# POWER_SUPPLY_20-100V.net
KiCad netlist of a schematic drawn in Altium Designer
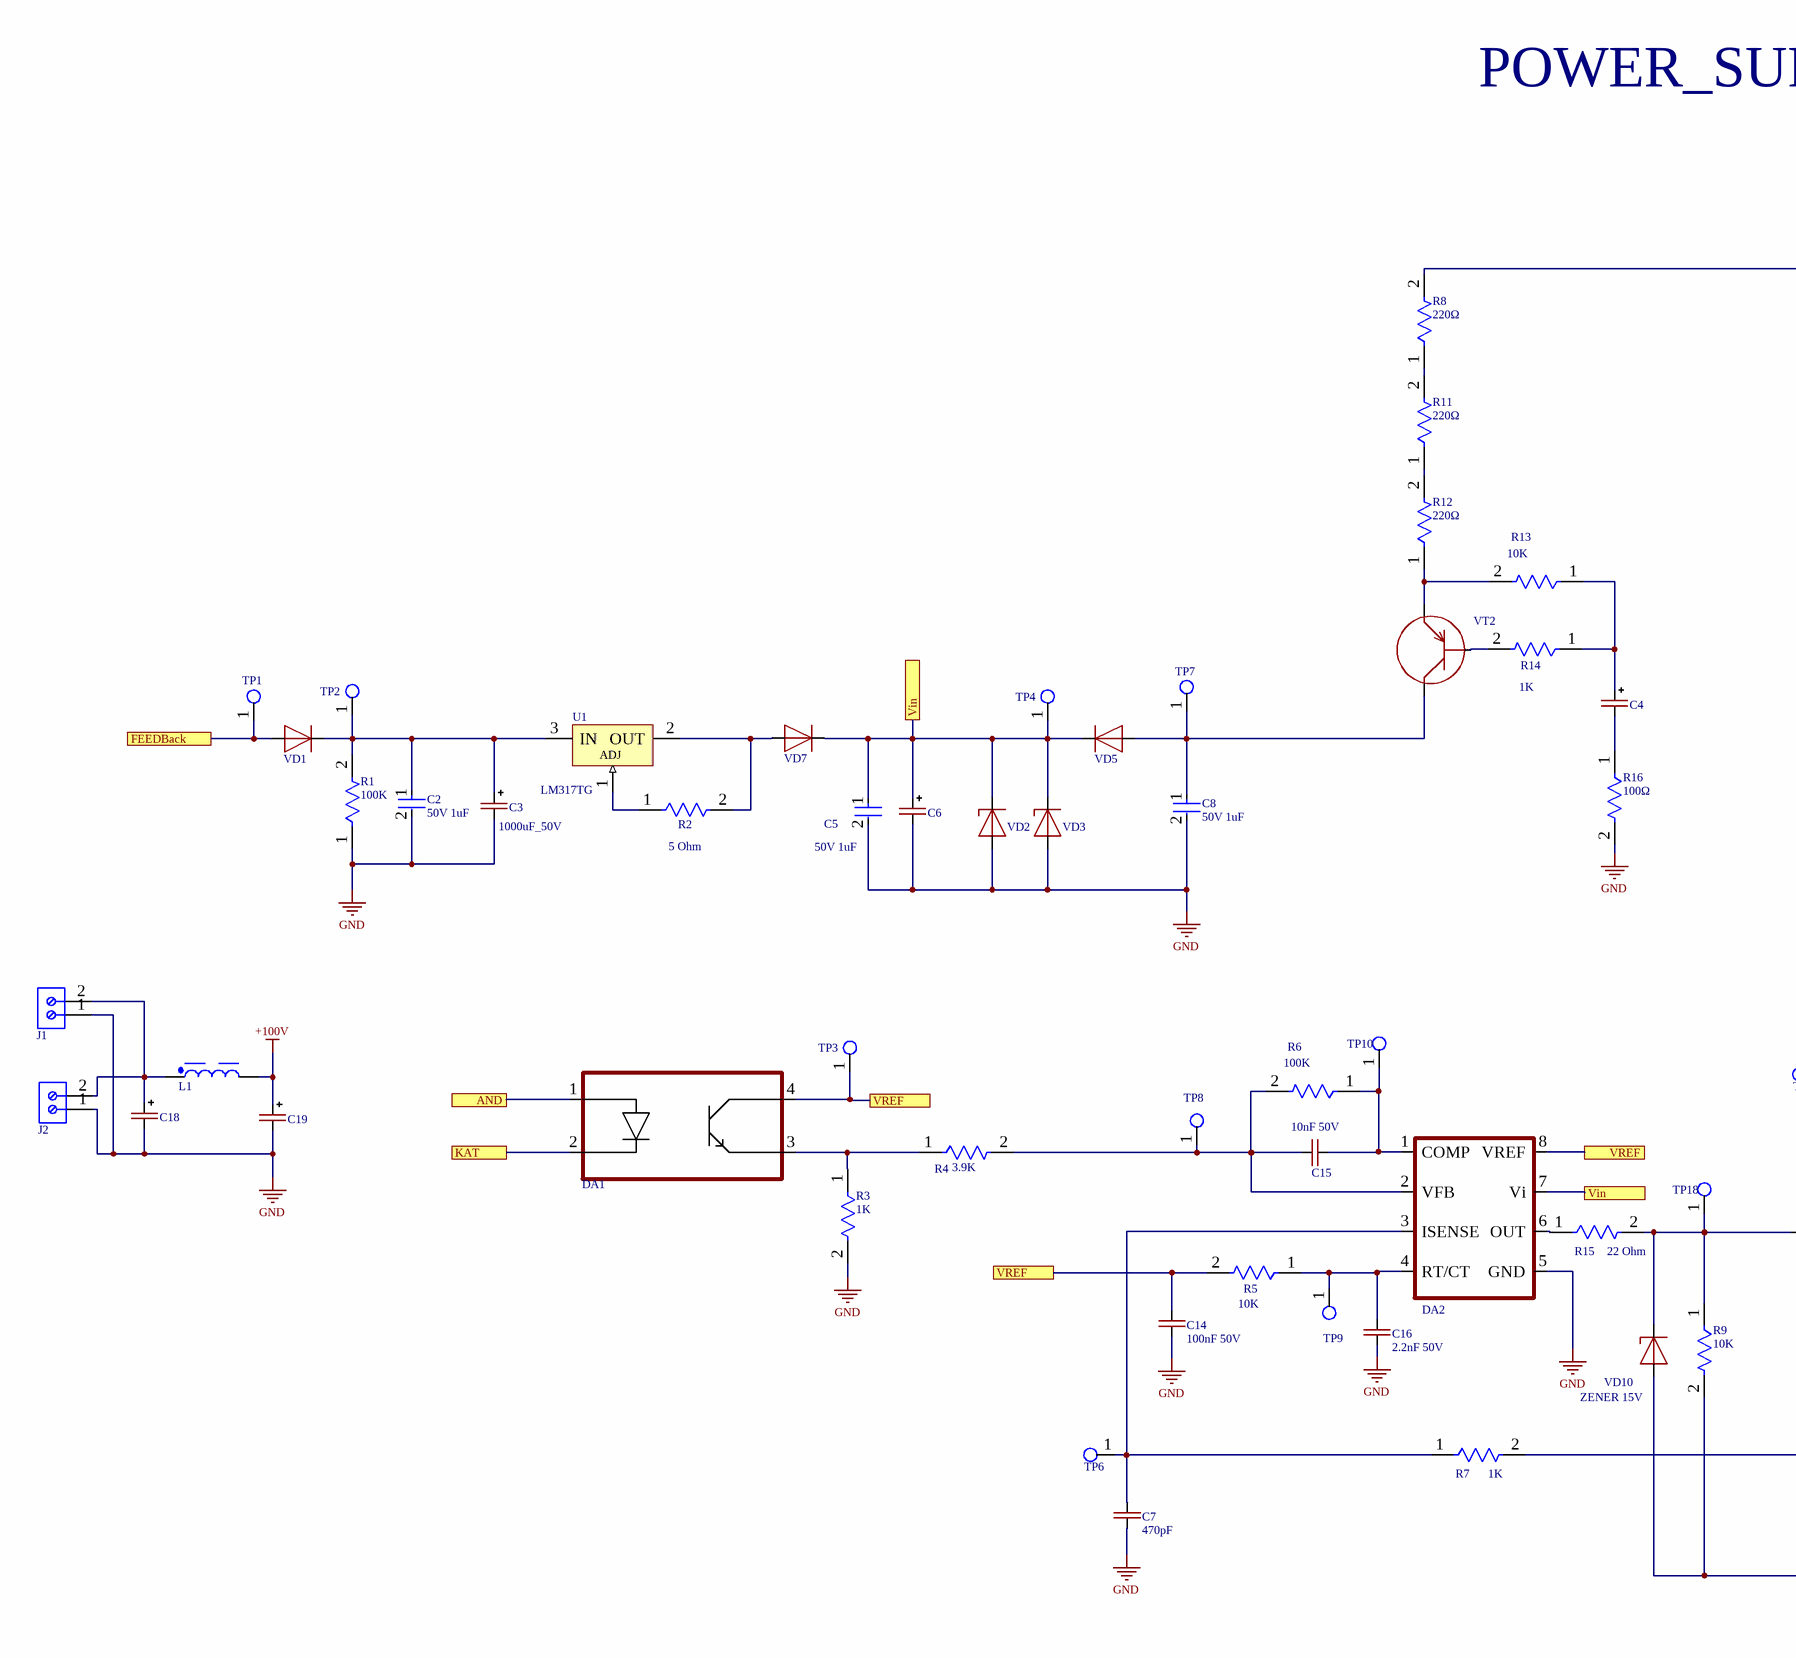
[diagram p0: POWER_SUPPLY_20-100V.SchDoc, left]
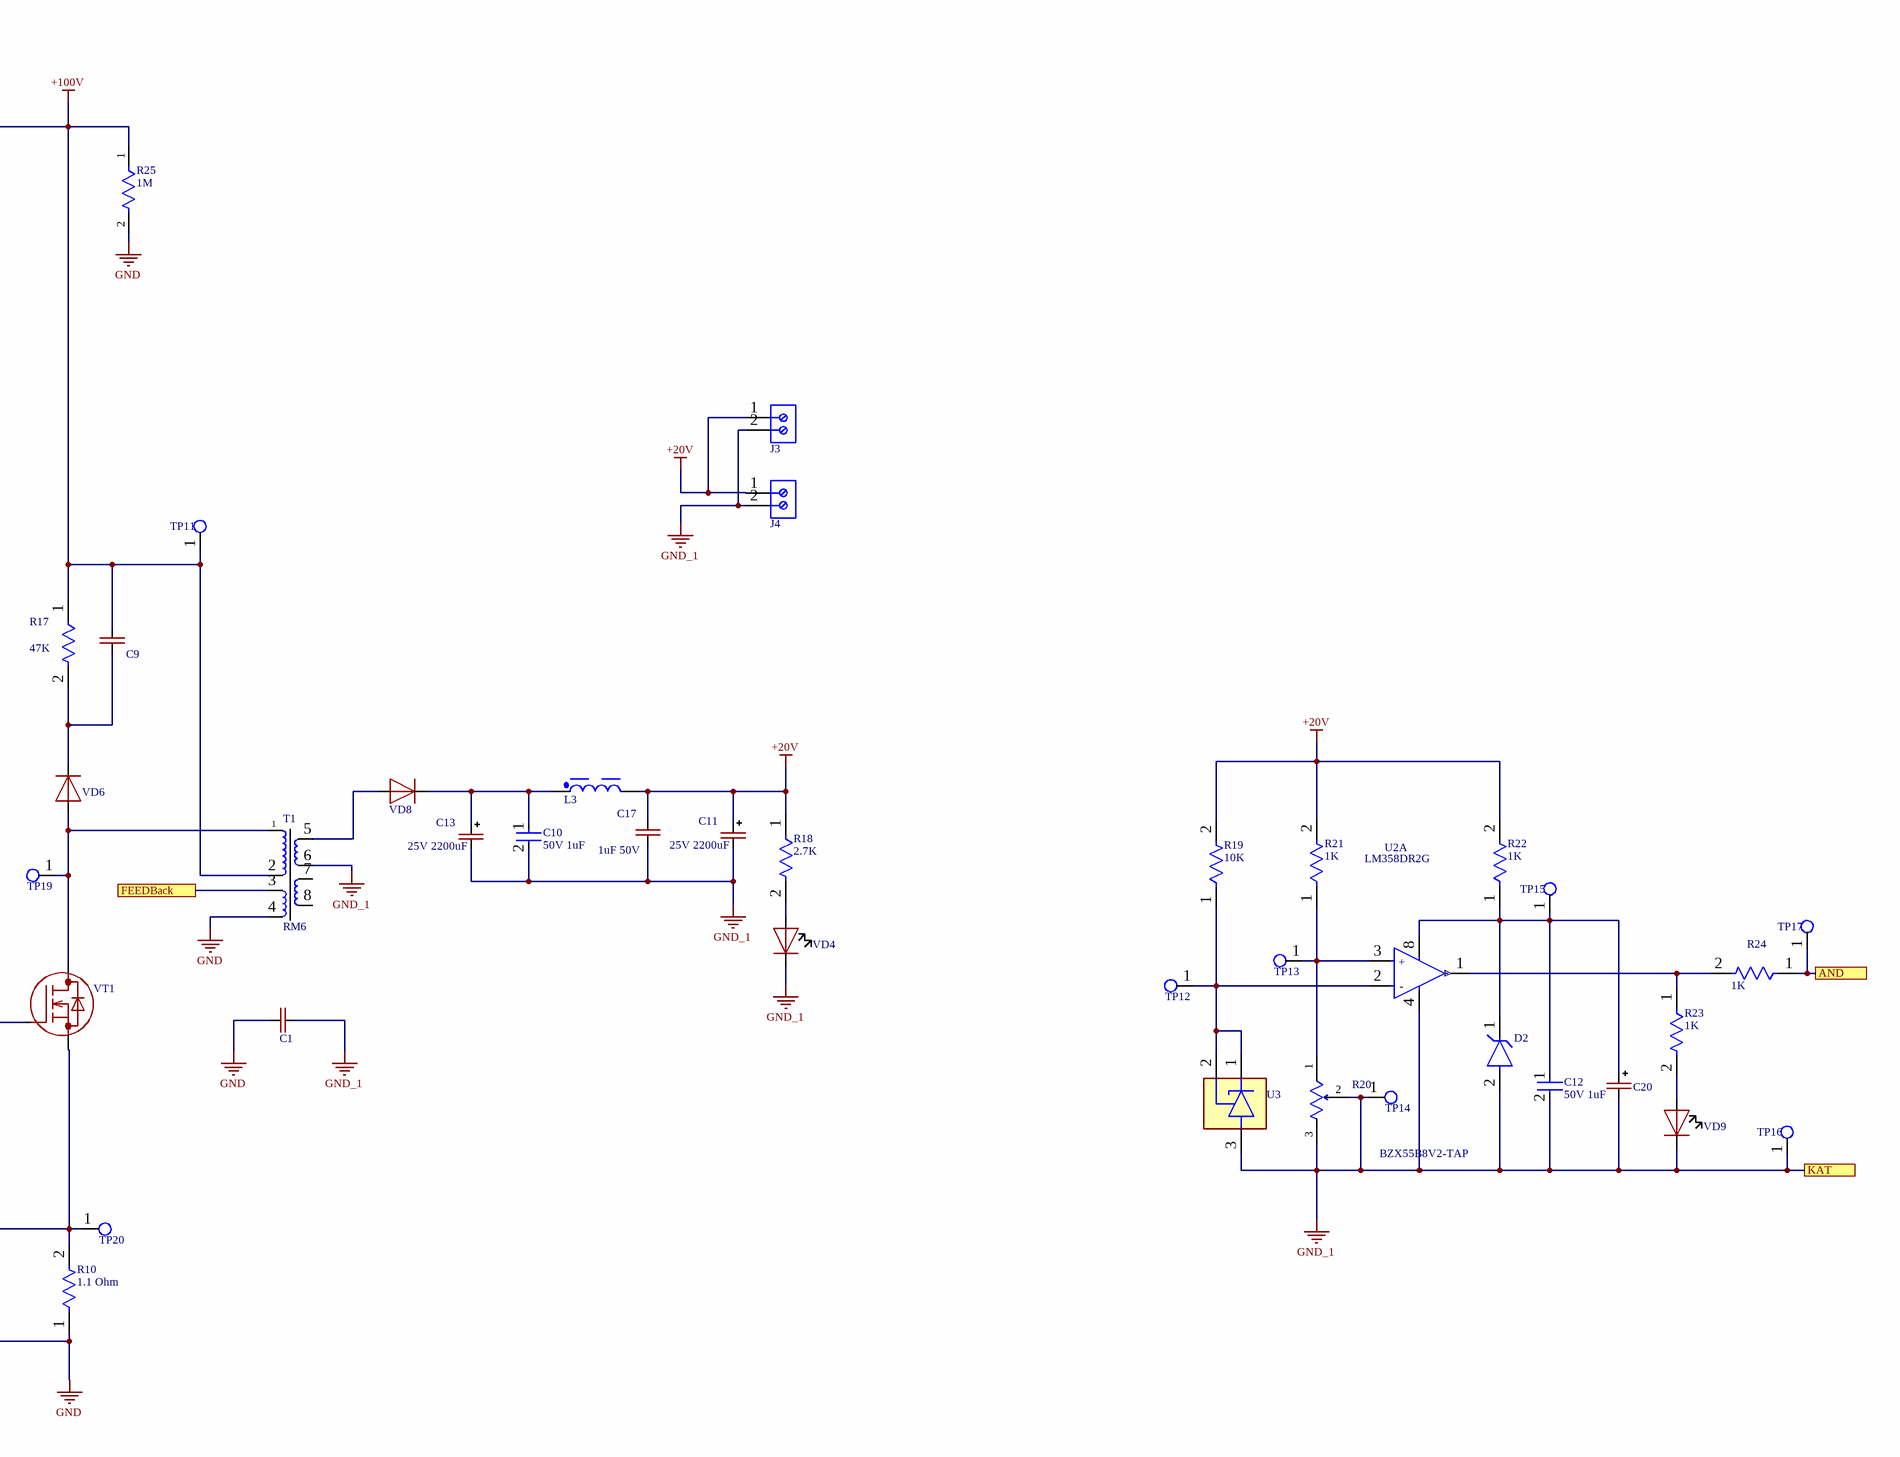
[diagram p1: POWER_SUPPLY_20-100V.SchDoc, right]

(export (version "E")
  (design (tool "Eeschema 10.0.6"))
  (components
    (comp (ref "C1")
      (value "CAP-NON-POLAR")
      (footprint "CAP-V5")
      (libsource (lib "2200pF") (part "CAP-NON-POLAR"))
    )
    (comp (ref "C2")
      (value "50V 1uF")
      (footprint "FP-C0805C-DN-IPC_A")
      (description "CAP CER 0.22UF 50V X7R 0805")
      (fields
        (field (name "MANUFACTURER") "KEMET")
        (field (name "OCTOPART") "https://octopart.com/c0805c224k5ractu-kemet-144670")
      )
      (libsource (lib "Pasive_components") (part "CMP-1036-04552-2"))
    )
    (comp (ref "C3")
      (value "1000uF_50V")
      (footprint "CAPPOL-12x25")
      (description "1000uF_50V  12x25(13x26mm)")
      (libsource (lib "PASSIVE_COMPONENTS") (part "CAP-POLAR"))
    )
    (comp (ref "C4")
      (value "CAP-POLAR")
      (footprint "CAPPOL-10x20")
      (libsource (lib "PASSIVE_COMPONENTS") (part "CAP-POLAR"))
    )
    (comp (ref "C5")
      (value "50V 1uF")
      (footprint "FP-C0805C-DN-IPC_A")
      (description "CAP CER 0.22UF 50V X7R 0805")
      (fields
        (field (name "MANUFACTURER") "KEMET")
        (field (name "OCTOPART") "https://octopart.com/c0805c224k5ractu-kemet-144670")
      )
      (libsource (lib "Pasive_components") (part "CMP-1036-04552-2"))
    )
    (comp (ref "C6")
      (value "CAP-POLAR")
      (footprint "CAPPOL-12x25")
      (libsource (lib "PASSIVE_COMPONENTS") (part "CAP-POLAR"))
    )
    (comp (ref "C7")
      (value "470pF")
      (footprint "CAP-0805")
      (libsource (lib "PASSIVE_COMPONENTS") (part "CAP-NON-POLAR"))
    )
    (comp (ref "C8")
      (value "50V 1uF")
      (footprint "FP-C0805C-DN-IPC_A")
      (description "CAP CER 0.22UF 50V X7R 0805")
      (fields
        (field (name "MANUFACTURER") "KEMET")
        (field (name "OCTOPART") "https://octopart.com/c0805c224k5ractu-kemet-144670")
      )
      (libsource (lib "Pasive_components") (part "CMP-1036-04552-2"))
    )
    (comp (ref "C9")
      (value "CAP-NON-POLAR")
      (footprint "CAP-V5")
      (libsource (lib "2200pF") (part "CAP-NON-POLAR"))
    )
    (comp (ref "C10")
      (value "50V 1uF")
      (footprint "FP-C0805C-DN-IPC_A")
      (description "CAP CER 0.22UF 50V X7R 0805")
      (fields
        (field (name "MANUFACTURER") "KEMET")
        (field (name "OCTOPART") "https://octopart.com/c0805c224k5ractu-kemet-144670")
      )
      (libsource (lib "Pasive_components") (part "CMP-1036-04552-2"))
    )
    (comp (ref "C11")
      (value "25V 2200uF")
      (footprint "CAPPOL-12x25")
      (libsource (lib "12.5X25") (part "CAP-POLAR"))
    )
    (comp (ref "C12")
      (value "50V 1uF")
      (footprint "FP-C0805C-DN-IPC_A")
      (description "CAP CER 0.22UF 50V X7R 0805")
      (fields
        (field (name "MANUFACTURER") "KEMET")
        (field (name "OCTOPART") "https://octopart.com/c0805c224k5ractu-kemet-144670")
      )
      (libsource (lib "Pasive_components") (part "CMP-1036-04552-2"))
    )
    (comp (ref "C13")
      (value "25V 2200uF")
      (footprint "CAPPOL-12x25")
      (libsource (lib "12.5X25") (part "CAP-POLAR"))
    )
    (comp (ref "C14")
      (value "100nF 50V")
      (footprint "CAP-0805")
      (libsource (lib "PASSIVE_COMPONENTS") (part "CAP-NON-POLAR"))
    )
    (comp (ref "C15")
      (value "10nF 50V")
      (footprint "CAP-0805")
      (libsource (lib "PASSIVE_COMPONENTS") (part "CAP-NON-POLAR"))
    )
    (comp (ref "C16")
      (value "2.2nF 50V")
      (footprint "CAP-0805")
      (libsource (lib "PASSIVE_COMPONENTS") (part "CAP-NON-POLAR"))
    )
    (comp (ref "C17")
      (value "1uF 50V")
      (footprint "CAP-0805")
      (libsource (lib "PASSIVE_COMPONENTS") (part "CAP-NON-POLAR"))
    )
    (comp (ref "C18")
      (value "CAP-POLAR")
      (footprint "CAPPOL-10x20")
      (libsource (lib "PASSIVE_COMPONENTS") (part "CAP-POLAR"))
    )
    (comp (ref "C19")
      (value "CAP-POLAR")
      (footprint "CAPPOL-10x20")
      (libsource (lib "PASSIVE_COMPONENTS") (part "CAP-POLAR"))
    )
    (comp (ref "C20")
      (value "CAP-POLAR")
      (footprint "CAP-TAN-D")
      (libsource (lib "PASSIVE_COMPONENTS") (part "CAP-POLAR"))
    )
    (comp (ref "D2")
      (value "BZX55B8V2-TAP")
      (footprint "FP-SB-V-3906_04-031_4-MFG")
      (description "DIODE ZENER 8.2V 500MW DO35")
      (fields (field (name "TOLERANCE") "2%"))
      (libsource (lib "Altium Content Vault") (part "f813f71cba58e380607f5dd3caf9714"))
    )
    (comp (ref "DA1") (value "PC817") (footprint "4-SMD") (libsource (lib "PC817") (part "PC817")))
    (comp (ref "DA2") (value "UC3842B") (footprint "SOIC8-150") (libsource (lib "UC3842B") (part "UC3842B")))
    (comp (ref "J1")
      (value "691101710002")
      (footprint "691101710002")
      (description "WR-TBL Series 101 Horizontal Entry Modular, THT, pitch 5mm, 2p")
      (fields (field (name "MANUFACTURER") "Wurth Elektronik"))
      (libsource (lib "Altium_WR-TBL (rev23d)") (part "691101710002"))
    )
    (comp (ref "J2")
      (value "691101710002")
      (footprint "691101710002")
      (description "WR-TBL Series 101 Horizontal Entry Modular, THT, pitch 5mm, 2p")
      (fields (field (name "MANUFACTURER") "Wurth Elektronik"))
      (libsource (lib "Altium_WR-TBL (rev23d)") (part "691101710002"))
    )
    (comp (ref "J3")
      (value "691101710002")
      (footprint "691101710002")
      (description "WR-TBL Series 101 Horizontal Entry Modular, THT, pitch 5mm, 2p")
      (fields (field (name "MANUFACTURER") "Wurth Elektronik"))
      (libsource (lib "Altium_WR-TBL (rev23d)") (part "691101710002"))
    )
    (comp (ref "J4")
      (value "691101710002")
      (footprint "691101710002")
      (description "WR-TBL Series 101 Horizontal Entry Modular, THT, pitch 5mm, 2p")
      (fields (field (name "MANUFACTURER") "Wurth Elektronik"))
      (libsource (lib "Altium_WR-TBL (rev23d)") (part "691101710002"))
    )
    (comp (ref "L1")
      (value "470µH, 0.36A")
      (footprint "WE-PD2_7850")
      (description "WE-PD2 SMT Power Inductor, size 7850, 470µH, 0.36A, 1.96Ω")
      (fields
        (field (name "MANUFACTURER PART NUMBER") "744775247")
        (field (name "MANUFACTURER") "Wurth Elektronik")
      )
      (libsource (lib "WE-PD2 (rev22d)") (part "744775247"))
    )
    (comp (ref "L3")
      (value "470µH, 0.36A")
      (footprint "WE-PD2_7850")
      (description "WE-PD2 SMT Power Inductor, size 7850, 470µH, 0.36A, 1.96Ω")
      (fields
        (field (name "MANUFACTURER PART NUMBER") "744775247")
        (field (name "MANUFACTURER") "Wurth Elektronik")
      )
      (libsource (lib "WE-PD2 (rev22d)") (part "744775247"))
    )
    (comp (ref "R1")
      (value "100K")
      (footprint "RES-0805")
      (libsource (lib "PASSIVE_COMPONENTS") (part "RES-CONST"))
    )
    (comp (ref "R2")
      (value "5 Ohm")
      (footprint "RES-1206")
      (libsource (lib "PASSIVE_COMPONENTS") (part "RES-CONST"))
    )
    (comp (ref "R3")
      (value "1K")
      (footprint "RES-0805")
      (libsource (lib "PASSIVE_COMPONENTS") (part "RES-CONST"))
    )
    (comp (ref "R4")
      (value "3.9K")
      (footprint "RES-0805")
      (libsource (lib "PASSIVE_COMPONENTS") (part "RES-CONST"))
    )
    (comp (ref "R5")
      (value "10K")
      (footprint "RES-0805")
      (libsource (lib "PASSIVE_COMPONENTS") (part "RES-CONST"))
    )
    (comp (ref "R6")
      (value "100K")
      (footprint "RES-0805")
      (libsource (lib "PASSIVE_COMPONENTS") (part "RES-CONST"))
    )
    (comp (ref "R7")
      (value "1K")
      (footprint "RES-0805")
      (libsource (lib "PASSIVE_COMPONENTS") (part "RES-CONST"))
    )
    (comp (ref "R8")
      (value "220Ω")
      (footprint "RES-2512")
      (libsource (lib "PASSIVE_COMPONENTS") (part "RES-CONST"))
    )
    (comp (ref "R9")
      (value "10K")
      (footprint "RES-0805")
      (libsource (lib "PASSIVE_COMPONENTS") (part "RES-CONST"))
    )
    (comp (ref "R10")
      (value "1.1 Ohm")
      (footprint "RES-2W")
      (libsource (lib "PASSIVE_COMPONENTS") (part "RES-CONST"))
    )
    (comp (ref "R11")
      (value "220Ω")
      (footprint "RES-2512")
      (libsource (lib "PASSIVE_COMPONENTS") (part "RES-CONST"))
    )
    (comp (ref "R12")
      (value "220Ω")
      (footprint "RES-2512")
      (libsource (lib "PASSIVE_COMPONENTS") (part "RES-CONST"))
    )
    (comp (ref "R13")
      (value "10K")
      (footprint "RES-0805")
      (libsource (lib "PASSIVE_COMPONENTS") (part "RES-CONST"))
    )
    (comp (ref "R14")
      (value "1K")
      (footprint "RES-0805")
      (libsource (lib "PASSIVE_COMPONENTS") (part "RES-CONST"))
    )
    (comp (ref "R15")
      (value "22 Ohm")
      (footprint "RES-0805")
      (libsource (lib "PASSIVE_COMPONENTS") (part "RES-CONST"))
    )
    (comp (ref "R16")
      (value "100Ω")
      (footprint "RES-0805")
      (libsource (lib "PASSIVE_COMPONENTS") (part "RES-CONST"))
    )
    (comp (ref "R17")
      (value "47K")
      (footprint "RES-0805")
      (libsource (lib "PASSIVE_COMPONENTS") (part "RES-CONST"))
    )
    (comp (ref "R18")
      (value "2.7K")
      (footprint "RES-0805")
      (libsource (lib "PASSIVE_COMPONENTS") (part "RES-CONST"))
    )
    (comp (ref "R19")
      (value "10K")
      (footprint "RES-0805")
      (libsource (lib "PASSIVE_COMPONENTS") (part "RES-CONST"))
    )
    (comp (ref "R20")
      (value "3296W-1-202LF")
      (footprint "Bourns_3296W_MFG")
      (libsource (lib "Pasive_components") (part "3296W-1-202LF"))
    )
    (comp (ref "R21")
      (value "1K")
      (footprint "RES-0805")
      (libsource (lib "PASSIVE_COMPONENTS") (part "RES-CONST"))
    )
    (comp (ref "R22")
      (value "1K")
      (footprint "RES-0805")
      (libsource (lib "PASSIVE_COMPONENTS") (part "RES-CONST"))
    )
    (comp (ref "R23")
      (value "1K")
      (footprint "RES-0805")
      (libsource (lib "PASSIVE_COMPONENTS") (part "RES-CONST"))
    )
    (comp (ref "R24")
      (value "1K")
      (footprint "RES-0805")
      (libsource (lib "PASSIVE_COMPONENTS") (part "RES-CONST"))
    )
    (comp (ref "R25")
      (value "1M")
      (footprint "Vishay_CRCW0805-e3_IPC_A")
      (libsource (lib "Res_Vishay_CRCW08050000Z0EA_eec") (part "CRCW08050000Z0EA"))
    )
    (comp (ref "T1")
      (value "RM6")
      (footprint "TRANS_RM6")
      (libsource (lib "Transformers") (part "Trans_RM6"))
    )
    (comp (ref "TP1")
      (value "Test_Point_PCB")
      (footprint "Test_Point")
      (description "Test_Point")
      (libsource (lib "Test_Point") (part "TP_PCB?"))
    )
    (comp (ref "TP2")
      (value "Test_Point_PCB")
      (footprint "Test_Point")
      (description "Test_Point")
      (libsource (lib "Test_Point") (part "TP_PCB?"))
    )
    (comp (ref "TP3")
      (value "Test_Point_PCB")
      (footprint "Test_Point")
      (description "Test_Point")
      (libsource (lib "Test_Point") (part "TP_PCB?"))
    )
    (comp (ref "TP4")
      (value "Test_Point_PCB")
      (footprint "Test_Point")
      (description "Test_Point")
      (libsource (lib "Test_Point") (part "TP_PCB?"))
    )
    (comp (ref "TP6")
      (value "Test_Point_PCB")
      (footprint "Test_Point")
      (description "Test_Point")
      (libsource (lib "Test_Point") (part "TP_PCB?"))
    )
    (comp (ref "TP7")
      (value "Test_Point_PCB")
      (footprint "Test_Point")
      (description "Test_Point")
      (libsource (lib "Test_Point") (part "TP_PCB?"))
    )
    (comp (ref "TP8")
      (value "Test_Point_PCB")
      (footprint "Test_Point")
      (description "Test_Point")
      (libsource (lib "Test_Point") (part "TP_PCB?"))
    )
    (comp (ref "TP9")
      (value "Test_Point_PCB")
      (footprint "Test_Point")
      (description "Test_Point")
      (libsource (lib "Test_Point") (part "TP_PCB?"))
    )
    (comp (ref "TP10")
      (value "Test_Point_PCB")
      (footprint "Test_Point")
      (description "Test_Point")
      (libsource (lib "Test_Point") (part "TP_PCB?"))
    )
    (comp (ref "TP11")
      (value "Test_Point_PCB")
      (footprint "Test_Point")
      (description "Test_Point")
      (libsource (lib "Test_Point") (part "TP_PCB?"))
    )
    (comp (ref "TP12")
      (value "Test_Point_PCB")
      (footprint "Test_Point")
      (description "Test_Point")
      (libsource (lib "Test_Point") (part "TP_PCB?"))
    )
    (comp (ref "TP13")
      (value "Test_Point_PCB")
      (footprint "Test_Point")
      (description "Test_Point")
      (libsource (lib "Test_Point") (part "TP_PCB?"))
    )
    (comp (ref "TP14")
      (value "Test_Point_PCB")
      (footprint "Test_Point")
      (description "Test_Point")
      (libsource (lib "Test_Point") (part "TP_PCB?"))
    )
    (comp (ref "TP15")
      (value "Test_Point_PCB")
      (footprint "Test_Point")
      (description "Test_Point")
      (libsource (lib "Test_Point") (part "TP_PCB?"))
    )
    (comp (ref "TP16")
      (value "Test_Point_PCB")
      (footprint "Test_Point")
      (description "Test_Point")
      (libsource (lib "Test_Point") (part "TP_PCB?"))
    )
    (comp (ref "TP17")
      (value "Test_Point_PCB")
      (footprint "Test_Point")
      (description "Test_Point")
      (libsource (lib "Test_Point") (part "TP_PCB?"))
    )
    (comp (ref "TP18")
      (value "Test_Point_PCB")
      (footprint "Test_Point")
      (description "Test_Point")
      (libsource (lib "Test_Point") (part "TP_PCB?"))
    )
    (comp (ref "TP19")
      (value "Test_Point_PCB")
      (footprint "Test_Point")
      (description "Test_Point")
      (libsource (lib "Test_Point") (part "TP_PCB?"))
    )
    (comp (ref "TP20")
      (value "Test_Point_PCB")
      (footprint "Test_Point")
      (description "Test_Point")
      (libsource (lib "Test_Point") (part "TP_PCB?"))
    )
    (comp (ref "U1")
      (value "LM317TG")
      (footprint "TO-220_Bended_Rad")
      (libsource (lib "LM317TG") (part "LM317TG"))
    )
    (comp (ref "U2")
      (value "LM358DR2G")
      (footprint "FP-751-07-IPC_C")
      (description "IC OPAMP GP 2 CIRCUIT 8SOIC")
      (libsource (lib "Altium Content Vault") (part "992a6607d1d88c80ee6b45e5ba6cb1b"))
    )
    (comp (ref "U3")
      (value "TL431")
      (footprint "TL431_SOT-23-3(MGF)")
      (description "TL431_SOT-23-3")
      (libsource (lib "TL431") (part "TL431_SOT-23-3"))
    )
    (comp (ref "VD1") (value "DIODE") (footprint "DO-214AC, SMA") (libsource (lib "DO214") (part "DIODE")))
    (comp (ref "VD2") (value "ZENER") (footprint "DO-017AA") (libsource (lib "ZENER") (part "ZENER")))
    (comp (ref "VD3") (value "ZENER") (footprint "DO-017AA") (libsource (lib "ZENER") (part "ZENER")))
    (comp (ref "VD4") (value "LED") (footprint "LED-0603") (libsource (lib "LED") (part "LED")))
    (comp (ref "VD5") (value "DIODE") (footprint "DO-214AC, SMA") (libsource (lib "DO214") (part "DIODE")))
    (comp (ref "VD6") (value "DIODE") (footprint "DO-214AC, SMA") (libsource (lib "DO214") (part "DIODE")))
    (comp (ref "VD7") (value "DIODE") (footprint "DO-214AC, SMA") (libsource (lib "DO214") (part "DIODE")))
    (comp (ref "VD8") (value "DIODE") (footprint "DO-214AC, SMA") (libsource (lib "DO214") (part "DIODE")))
    (comp (ref "VD9") (value "LED") (footprint "LED-0603") (libsource (lib "LED") (part "LED")))
    (comp (ref "VD10") (value "ZENER 15V") (footprint "DO-017AA") (libsource (lib "ZENER") (part "ZENER")))
    (comp (ref "VT1")
      (value "MOSFET-N-GDS")
      (footprint "TO-220_Bended_Rad")
      (libsource (lib "IRF640") (part "MOSFET-N-GDS"))
    )
    (comp (ref "VT2")
      (value "BIPOLAR-PNP-BCE")
      (footprint "SOT-223-3")
      (libsource (lib "PBHV9040") (part "BIPOLAR-PNP-BCE"))
    )
  )
  (nets
    (net (code "1") (name "+20V") (class "Default")
      (node (ref "C11") (pin "1") (pinfunction "+_1") (pintype "passive"))
      (node (ref "C17") (pin "2") (pinfunction "2_2") (pintype "passive"))
      (node (ref "J3") (pin "1") (pinfunction "1_1") (pintype "passive"))
      (node (ref "J4") (pin "1") (pinfunction "1_1") (pintype "passive"))
      (node (ref "L3") (pin "2") (pinfunction "2_2") (pintype "passive"))
      (node (ref "R18") (pin "1") (pinfunction "1_1") (pintype "passive"))
      (node (ref "R19") (pin "2") (pinfunction "2_2") (pintype "passive"))
      (node (ref "R21") (pin "2") (pinfunction "2_2") (pintype "passive"))
      (node (ref "R22") (pin "2") (pinfunction "2_2") (pintype "passive"))
    )
    (net (code "2") (name "+100V") (class "Default")
      (node (ref "C19") (pin "1") (pinfunction "+_1") (pintype "passive"))
      (node (ref "C9") (pin "2") (pinfunction "2_2") (pintype "passive"))
      (node (ref "L1") (pin "2") (pinfunction "2_2") (pintype "passive"))
      (node (ref "R17") (pin "1") (pinfunction "1_1") (pintype "passive"))
      (node (ref "R25") (pin "1") (pinfunction "1_1") (pintype "passive"))
      (node (ref "R8") (pin "2") (pinfunction "2_2") (pintype "passive"))
      (node (ref "T1") (pin "2") (pinfunction "2_2") (pintype "passive"))
      (node (ref "TP11") (pin "1") (pinfunction "G9_1") (pintype "passive"))
    )
    (net (code "3") (name "/AND") (class "Default")
      (node (ref "DA1") (pin "1") (pinfunction "ANODE_1") (pintype "passive"))
      (node (ref "R24") (pin "1") (pinfunction "1_1") (pintype "passive"))
      (node (ref "TP17") (pin "1") (pinfunction "G9_1") (pintype "passive"))
    )
    (net (code "4") (name "/FEEDBack") (class "Default")
      (node (ref "T1") (pin "3") (pinfunction "3_3") (pintype "passive"))
      (node (ref "TP1") (pin "1") (pinfunction "G9_1") (pintype "passive"))
      (node (ref "VD1") (pin "2") (pinfunction "A_2") (pintype "passive"))
    )
    (net (code "5") (name "/VREF") (class "Default")
      (node (ref "C14") (pin "2") (pinfunction "2_2") (pintype "passive"))
      (node (ref "DA1") (pin "4") (pinfunction "COLLECTOR_4") (pintype "passive"))
      (node (ref "DA2") (pin "8") (pinfunction "VREF_8") (pintype "passive"))
      (node (ref "R5") (pin "2") (pinfunction "2_2") (pintype "passive"))
      (node (ref "TP3") (pin "1") (pinfunction "G9_1") (pintype "passive"))
    )
    (net (code "6") (name "/Vin") (class "Default")
      (node (ref "C5") (pin "1") (pinfunction "1_1") (pintype "passive"))
      (node (ref "C6") (pin "1") (pinfunction "+_1") (pintype "passive"))
      (node (ref "DA2") (pin "7") (pinfunction "Vi_7") (pintype "passive"))
      (node (ref "TP4") (pin "1") (pinfunction "G9_1") (pintype "passive"))
      (node (ref "VD2") (pin "1") (pinfunction "C_1") (pintype "passive"))
      (node (ref "VD3") (pin "1") (pinfunction "C_1") (pintype "passive"))
      (node (ref "VD5") (pin "1") (pinfunction "C_1") (pintype "passive"))
      (node (ref "VD7") (pin "1") (pinfunction "C_1") (pintype "passive"))
    )
    (net (code "7") (name "GND") (class "Default")
      (node (ref "C1") (pin "1") (pinfunction "1_1") (pintype "passive"))
      (node (ref "C14") (pin "1") (pinfunction "1_1") (pintype "passive"))
      (node (ref "C16") (pin "1") (pinfunction "1_1") (pintype "passive"))
      (node (ref "C18") (pin "2") (pinfunction "-_2") (pintype "passive"))
      (node (ref "C19") (pin "2") (pinfunction "-_2") (pintype "passive"))
      (node (ref "C2") (pin "2") (pinfunction "2_2") (pintype "passive"))
      (node (ref "C3") (pin "2") (pinfunction "-_2") (pintype "passive"))
      (node (ref "C5") (pin "2") (pinfunction "2_2") (pintype "passive"))
      (node (ref "C6") (pin "2") (pinfunction "-_2") (pintype "passive"))
      (node (ref "C7") (pin "1") (pinfunction "1_1") (pintype "passive"))
      (node (ref "C8") (pin "2") (pinfunction "2_2") (pintype "passive"))
      (node (ref "DA2") (pin "5") (pinfunction "GND_5") (pintype "passive"))
      (node (ref "J1") (pin "1") (pinfunction "1_1") (pintype "passive"))
      (node (ref "J2") (pin "1") (pinfunction "1_1") (pintype "passive"))
      (node (ref "R1") (pin "1") (pinfunction "1_1") (pintype "passive"))
      (node (ref "R10") (pin "1") (pinfunction "1_1") (pintype "passive"))
      (node (ref "R16") (pin "2") (pinfunction "2_2") (pintype "passive"))
      (node (ref "R25") (pin "2") (pinfunction "2_2") (pintype "passive"))
      (node (ref "R3") (pin "2") (pinfunction "2_2") (pintype "passive"))
      (node (ref "R9") (pin "2") (pinfunction "2_2") (pintype "passive"))
      (node (ref "T1") (pin "4") (pinfunction "4_4") (pintype "passive"))
      (node (ref "VD10") (pin "2") (pinfunction "A_2") (pintype "passive"))
      (node (ref "VD2") (pin "2") (pinfunction "A_2") (pintype "passive"))
      (node (ref "VD3") (pin "2") (pinfunction "A_2") (pintype "passive"))
    )
    (net (code "8") (name "GND_1") (class "Default")
      (node (ref "C1") (pin "2") (pinfunction "2_2") (pintype "passive"))
      (node (ref "C10") (pin "2") (pinfunction "2_2") (pintype "passive"))
      (node (ref "C11") (pin "2") (pinfunction "-_2") (pintype "passive"))
      (node (ref "C12") (pin "2") (pinfunction "2_2") (pintype "passive"))
      (node (ref "C13") (pin "2") (pinfunction "-_2") (pintype "passive"))
      (node (ref "C17") (pin "1") (pinfunction "1_1") (pintype "passive"))
      (node (ref "C20") (pin "2") (pinfunction "-_2") (pintype "passive"))
      (node (ref "D2") (pin "2") (pinfunction "A_2") (pintype "passive"))
      (node (ref "DA1") (pin "2") (pinfunction "CATHODE_2") (pintype "passive"))
      (node (ref "J3") (pin "2") (pinfunction "2_2") (pintype "passive"))
      (node (ref "J4") (pin "2") (pinfunction "2_2") (pintype "passive"))
      (node (ref "R20") (pin "2") (pinfunction "WIPER_2") (pintype "passive"))
      (node (ref "R20") (pin "3") (pinfunction "CW_3") (pintype "passive"))
      (node (ref "T1") (pin "6") (pinfunction "6_6") (pintype "passive"))
      (node (ref "TP14") (pin "1") (pinfunction "G9_1") (pintype "passive"))
      (node (ref "TP16") (pin "1") (pinfunction "G9_1") (pintype "passive"))
      (node (ref "U2") (pin "4") (pinfunction "VEE/GND_4") (pintype "power_in"))
      (node (ref "U3") (pin "3") (pinfunction "A_3") (pintype "passive"))
      (node (ref "VD4") (pin "1") (pinfunction "C_1") (pintype "passive"))
      (node (ref "VD9") (pin "1") (pinfunction "C_1") (pintype "passive"))
    )
    (net (code "9") (name "Net-(C3-+)") (class "Default")
      (node (ref "C2") (pin "1") (pinfunction "1_1") (pintype "passive"))
      (node (ref "C3") (pin "1") (pinfunction "+_1") (pintype "passive"))
      (node (ref "R1") (pin "2") (pinfunction "2_2") (pintype "passive"))
      (node (ref "TP2") (pin "1") (pinfunction "G9_1") (pintype "passive"))
      (node (ref "U1") (pin "3") (pinfunction "IN_3") (pintype "power_in"))
      (node (ref "VD1") (pin "1") (pinfunction "C_1") (pintype "passive"))
    )
    (net (code "10") (name "Net-(C4-+)") (class "Default")
      (node (ref "C4") (pin "1") (pinfunction "+_1") (pintype "passive"))
      (node (ref "R13") (pin "1") (pinfunction "1_1") (pintype "passive"))
      (node (ref "R14") (pin "1") (pinfunction "1_1") (pintype "passive"))
    )
    (net (code "11") (name "Net-(C4--)") (class "Default")
      (node (ref "C4") (pin "2") (pinfunction "-_2") (pintype "passive"))
      (node (ref "R16") (pin "1") (pinfunction "1_1") (pintype "passive"))
    )
    (net (code "12") (name "Net-(C13-+)") (class "Default")
      (node (ref "C10") (pin "1") (pinfunction "1_1") (pintype "passive"))
      (node (ref "C13") (pin "1") (pinfunction "+_1") (pintype "passive"))
      (node (ref "L3") (pin "1") (pinfunction "1_1") (pintype "passive"))
      (node (ref "VD8") (pin "1") (pinfunction "C_1") (pintype "passive"))
    )
    (net (code "13") (name "Net-(C18-+)") (class "Default")
      (node (ref "C18") (pin "1") (pinfunction "+_1") (pintype "passive"))
      (node (ref "J1") (pin "2") (pinfunction "2_2") (pintype "passive"))
      (node (ref "J2") (pin "2") (pinfunction "2_2") (pintype "passive"))
      (node (ref "L1") (pin "1") (pinfunction "1_1") (pintype "passive"))
    )
    (net (code "14") (name "Net-(C20-+)") (class "Default")
      (node (ref "C12") (pin "1") (pinfunction "1_1") (pintype "passive"))
      (node (ref "C20") (pin "1") (pinfunction "+_1") (pintype "passive"))
      (node (ref "D2") (pin "1") (pinfunction "C_1") (pintype "passive"))
      (node (ref "R22") (pin "1") (pinfunction "1_1") (pintype "passive"))
      (node (ref "TP15") (pin "1") (pinfunction "G9_1") (pintype "passive"))
      (node (ref "U2") (pin "8") (pinfunction "VCC_8") (pintype "power_in"))
    )
    (net (code "15") (name "Net-(DA1-EMITTER)") (class "Default")
      (node (ref "DA1") (pin "3") (pinfunction "EMITTER_3") (pintype "passive"))
      (node (ref "R3") (pin "1") (pinfunction "1_1") (pintype "passive"))
      (node (ref "R4") (pin "1") (pinfunction "1_1") (pintype "passive"))
    )
    (net (code "16") (name "Net-(DA2-COMP)") (class "Default")
      (node (ref "C15") (pin "2") (pinfunction "2_2") (pintype "passive"))
      (node (ref "DA2") (pin "1") (pinfunction "COMP_1") (pintype "passive"))
      (node (ref "R6") (pin "1") (pinfunction "1_1") (pintype "passive"))
      (node (ref "TP10") (pin "1") (pinfunction "G9_1") (pintype "passive"))
    )
    (net (code "17") (name "Net-(DA2-ISENSE)") (class "Default")
      (node (ref "C7") (pin "2") (pinfunction "2_2") (pintype "passive"))
      (node (ref "DA2") (pin "3") (pinfunction "ISENSE_3") (pintype "passive"))
      (node (ref "R7") (pin "1") (pinfunction "1_1") (pintype "passive"))
      (node (ref "TP6") (pin "1") (pinfunction "G9_1") (pintype "passive"))
    )
    (net (code "18") (name "Net-(DA2-OUT)") (class "Default")
      (node (ref "DA2") (pin "6") (pinfunction "OUT_6") (pintype "passive"))
      (node (ref "R15") (pin "1") (pinfunction "1_1") (pintype "passive"))
    )
    (net (code "19") (name "Net-(DA2-RT{slash}CT)") (class "Default")
      (node (ref "C16") (pin "2") (pinfunction "2_2") (pintype "passive"))
      (node (ref "DA2") (pin "4") (pinfunction "RT/CT_4") (pintype "passive"))
      (node (ref "R5") (pin "1") (pinfunction "1_1") (pintype "passive"))
      (node (ref "TP9") (pin "1") (pinfunction "G9_1") (pintype "passive"))
    )
    (net (code "20") (name "Net-(DA2-VFB)") (class "Default")
      (node (ref "C15") (pin "1") (pinfunction "1_1") (pintype "passive"))
      (node (ref "DA2") (pin "2") (pinfunction "VFB_2") (pintype "passive"))
      (node (ref "R4") (pin "2") (pinfunction "2_2") (pintype "passive"))
      (node (ref "R6") (pin "2") (pinfunction "2_2") (pintype "passive"))
      (node (ref "TP8") (pin "1") (pinfunction "G9_1") (pintype "passive"))
    )
    (net (code "21") (name "Net-(R11-Pad1)") (class "Default")
      (node (ref "R11") (pin "1") (pinfunction "1_1") (pintype "passive"))
      (node (ref "R12") (pin "2") (pinfunction "2_2") (pintype "passive"))
    )
    (net (code "22") (name "Net-(R11-Pad2)") (class "Default")
      (node (ref "R11") (pin "2") (pinfunction "2_2") (pintype "passive"))
      (node (ref "R8") (pin "1") (pinfunction "1_1") (pintype "passive"))
    )
    (net (code "23") (name "Net-(R20-CCW)") (class "Default")
      (node (ref "R20") (pin "1") (pinfunction "CCW_1") (pintype "passive"))
      (node (ref "R21") (pin "1") (pinfunction "1_1") (pintype "passive"))
      (node (ref "TP13") (pin "1") (pinfunction "G9_1") (pintype "passive"))
      (node (ref "U2") (pin "3") (pinfunction "INPUT_A+_3") (pintype "tri_state"))
    )
    (net (code "24") (name "Net-(TP7-G9)") (class "Default")
      (node (ref "C8") (pin "1") (pinfunction "1_1") (pintype "passive"))
      (node (ref "TP7") (pin "1") (pinfunction "G9_1") (pintype "passive"))
      (node (ref "VD5") (pin "2") (pinfunction "A_2") (pintype "passive"))
      (node (ref "VT2") (pin "2") (pinfunction "C_2") (pintype "passive"))
    )
    (net (code "25") (name "Net-(TP12-G9)") (class "Default")
      (node (ref "R19") (pin "1") (pinfunction "1_1") (pintype "passive"))
      (node (ref "TP12") (pin "1") (pinfunction "G9_1") (pintype "passive"))
      (node (ref "U2") (pin "2") (pinfunction "INPUT_A-_2") (pintype "tri_state"))
      (node (ref "U3") (pin "1") (pinfunction "C_1") (pintype "passive"))
      (node (ref "U3") (pin "2") (pinfunction "REF_2") (pintype "passive"))
    )
    (net (code "26") (name "Net-(TP18-G9)") (class "Default")
      (node (ref "R15") (pin "2") (pinfunction "2_2") (pintype "passive"))
      (node (ref "R9") (pin "1") (pinfunction "1_1") (pintype "passive"))
      (node (ref "TP18") (pin "1") (pinfunction "G9_1") (pintype "passive"))
      (node (ref "VD10") (pin "1") (pinfunction "C_1") (pintype "passive"))
      (node (ref "VT1") (pin "1") (pinfunction "G_1") (pintype "passive"))
    )
    (net (code "27") (name "Net-(TP19-G9)") (class "Default")
      (node (ref "T1") (pin "1") (pinfunction "1_1") (pintype "passive"))
      (node (ref "TP19") (pin "1") (pinfunction "G9_1") (pintype "passive"))
      (node (ref "VD6") (pin "2") (pinfunction "A_2") (pintype "passive"))
      (node (ref "VT1") (pin "2") (pinfunction "D_2") (pintype "passive"))
    )
    (net (code "28") (name "Net-(TP20-G9)") (class "Default")
      (node (ref "R10") (pin "2") (pinfunction "2_2") (pintype "passive"))
      (node (ref "R7") (pin "2") (pinfunction "2_2") (pintype "passive"))
      (node (ref "TP20") (pin "1") (pinfunction "G9_1") (pintype "passive"))
      (node (ref "VT1") (pin "3") (pinfunction "S_3") (pintype "passive"))
    )
    (net (code "29") (name "Net-(U1-ADJ)") (class "Default")
      (node (ref "R2") (pin "1") (pinfunction "1_1") (pintype "passive"))
      (node (ref "U1") (pin "1") (pinfunction "ADJ_1") (pintype "input"))
    )
    (net (code "30") (name "Net-(U1-OUT)") (class "Default")
      (node (ref "R2") (pin "2") (pinfunction "2_2") (pintype "passive"))
      (node (ref "U1") (pin "2") (pinfunction "OUT_2") (pintype "power_in"))
      (node (ref "VD7") (pin "2") (pinfunction "A_2") (pintype "passive"))
    )
    (net (code "31") (name "Net-(U2A-OUTPUT_A)") (class "Default")
      (node (ref "R23") (pin "1") (pinfunction "1_1") (pintype "passive"))
      (node (ref "R24") (pin "2") (pinfunction "2_2") (pintype "passive"))
      (node (ref "U2") (pin "1") (pinfunction "OUTPUT_A_1") (pintype "output"))
    )
    (net (code "32") (name "Net-(VD4-A)") (class "Default")
      (node (ref "R18") (pin "2") (pinfunction "2_2") (pintype "passive"))
      (node (ref "VD4") (pin "2") (pinfunction "A_2") (pintype "passive"))
    )
    (net (code "33") (name "Net-(VD6-C)") (class "Default")
      (node (ref "C9") (pin "1") (pinfunction "1_1") (pintype "passive"))
      (node (ref "R17") (pin "2") (pinfunction "2_2") (pintype "passive"))
      (node (ref "VD6") (pin "1") (pinfunction "C_1") (pintype "passive"))
    )
    (net (code "34") (name "Net-(VD8-A)") (class "Default")
      (node (ref "T1") (pin "5") (pinfunction "5_5") (pintype "passive"))
      (node (ref "VD8") (pin "2") (pinfunction "A_2") (pintype "passive"))
    )
    (net (code "35") (name "Net-(VD9-A)") (class "Default")
      (node (ref "R23") (pin "2") (pinfunction "2_2") (pintype "passive"))
      (node (ref "VD9") (pin "2") (pinfunction "A_2") (pintype "passive"))
    )
    (net (code "36") (name "Net-(VT2-B)") (class "Default")
      (node (ref "R14") (pin "2") (pinfunction "2_2") (pintype "passive"))
      (node (ref "VT2") (pin "1") (pinfunction "B_1") (pintype "passive"))
    )
    (net (code "37") (name "Net-(VT2-E)") (class "Default")
      (node (ref "R12") (pin "1") (pinfunction "1_1") (pintype "passive"))
      (node (ref "R13") (pin "2") (pinfunction "2_2") (pintype "passive"))
      (node (ref "VT2") (pin "3") (pinfunction "E_3") (pintype "passive"))
    )
    (net (code "38") (name "unconnected-(T1-Pad7)") (class "Default")
      (node (ref "T1") (pin "7") (pinfunction "7_7") (pintype "passive"))
    )
    (net (code "39") (name "unconnected-(T1-Pad8)") (class "Default")
      (node (ref "T1") (pin "8") (pinfunction "8_8") (pintype "passive"))
    )
  )
)
